# EXT_DIMMER.net
KiCad netlist of a schematic drawn in EAGLE
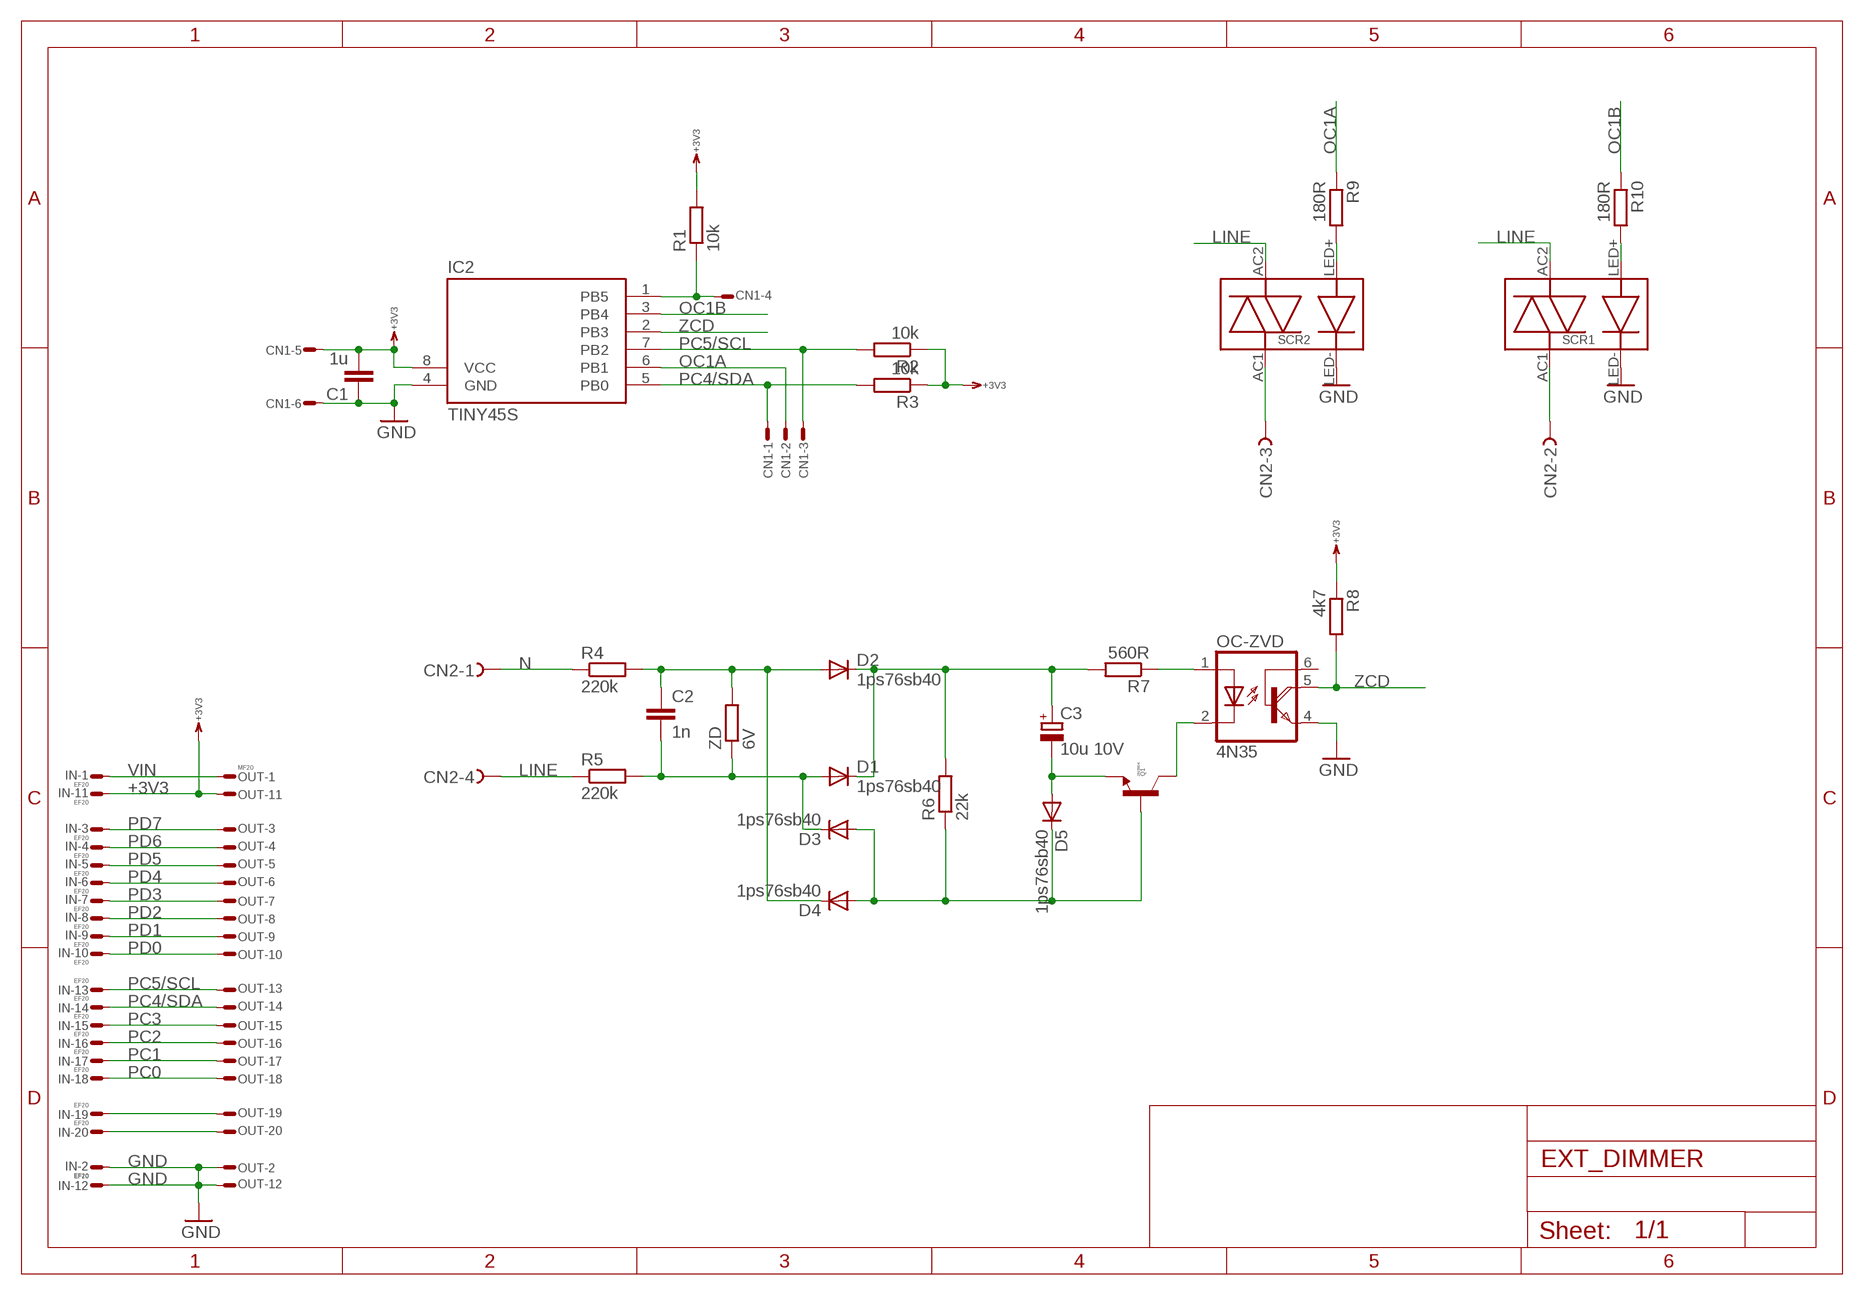
[diagram p0: schematic, sheet 1]

(export (version "E")
  (design (tool "Eeschema 10.0.6"))
  (components
    (comp (ref "C1")
      (value "1u")
      (footprint "eagle-import:0603")
      (libsource (lib "eagle-import") (part "C0603"))
    )
    (comp (ref "C2")
      (value "1n")
      (footprint "eagle-import:1206")
      (libsource (lib "eagle-import") (part "C1206"))
    )
    (comp (ref "C3")
      (value "10u 10V")
      (footprint "eagle-import:SMC_A")
      (libsource (lib "eagle-import") (part "C_POLSMCA"))
    )
    (comp (ref "CN1")
      (value "CON6N")
      (footprint "eagle-import:CON6")
      (libsource (lib "eagle-import") (part "CON6N"))
    )
    (comp (ref "CN2")
      (value "CON4-S")
      (footprint "eagle-import:CTB9308")
      (libsource (lib "eagle-import") (part "CON4-S"))
    )
    (comp (ref "D1")
      (value "1ps76sb40")
      (footprint "eagle-import:SOD323")
      (libsource (lib "eagle-import") (part "DSOD323"))
    )
    (comp (ref "D2")
      (value "1ps76sb40")
      (footprint "eagle-import:SOD323")
      (libsource (lib "eagle-import") (part "DSOD323"))
    )
    (comp (ref "D3")
      (value "1ps76sb40")
      (footprint "eagle-import:SOD323")
      (libsource (lib "eagle-import") (part "DSOD323"))
    )
    (comp (ref "D4")
      (value "1ps76sb40")
      (footprint "eagle-import:SOD323")
      (libsource (lib "eagle-import") (part "DSOD323"))
    )
    (comp (ref "D5")
      (value "1ps76sb40")
      (footprint "eagle-import:SOD323")
      (libsource (lib "eagle-import") (part "DSOD323"))
    )
    (comp (ref "IC2")
      (value "TINY45S")
      (footprint "eagle-import:SOIC8")
      (libsource (lib "eagle-import") (part "TINY45S"))
    )
    (comp (ref "IN")
      (value "EF20")
      (footprint "eagle-import:FE10-2WSS")
      (libsource (lib "eagle-import") (part "FE20ELSS"))
    )
    (comp (ref "OC-ZVD")
      (value "4N35")
      (footprint "eagle-import:DIL06")
      (fields (field (name "MF") "VISHAY/TELEFUNKEN") (field (name "MPN") "4N33"))
      (libsource (lib "eagle-import") (part "OC-NPN"))
    )
    (comp (ref "OUT")
      (value "MF20")
      (footprint "eagle-import:ML20LS")
      (libsource (lib "eagle-import") (part "ML20?ELS"))
    )
    (comp (ref "Q1")
      (value "2N3904")
      (footprint "eagle-import:SOT23")
      (libsource (lib "eagle-import") (part "NPN23"))
    )
    (comp (ref "R1")
      (value "10k")
      (footprint "eagle-import:0603")
      (libsource (lib "eagle-import") (part "R0603"))
    )
    (comp (ref "R2")
      (value "10k")
      (footprint "eagle-import:0603")
      (libsource (lib "eagle-import") (part "R0603"))
    )
    (comp (ref "R3")
      (value "10k")
      (footprint "eagle-import:0603")
      (libsource (lib "eagle-import") (part "R0603"))
    )
    (comp (ref "R4")
      (value "220k")
      (footprint "eagle-import:1206")
      (libsource (lib "eagle-import") (part "R1206"))
    )
    (comp (ref "R5")
      (value "220k")
      (footprint "eagle-import:1206")
      (libsource (lib "eagle-import") (part "R1206"))
    )
    (comp (ref "R6")
      (value "22k")
      (footprint "eagle-import:0603")
      (libsource (lib "eagle-import") (part "R0603"))
    )
    (comp (ref "R7")
      (value "560R")
      (footprint "eagle-import:0603")
      (libsource (lib "eagle-import") (part "R0603"))
    )
    (comp (ref "R8")
      (value "4k7")
      (footprint "eagle-import:0603")
      (libsource (lib "eagle-import") (part "R0603"))
    )
    (comp (ref "R9")
      (value "180R")
      (footprint "eagle-import:0603")
      (libsource (lib "eagle-import") (part "R0603"))
    )
    (comp (ref "R10")
      (value "180R")
      (footprint "eagle-import:0603")
      (libsource (lib "eagle-import") (part "R0603"))
    )
    (comp (ref "SCR1")
      (value "S202")
      (footprint "eagle-import:S202")
      (libsource (lib "eagle-import") (part "S202"))
    )
    (comp (ref "SCR2")
      (value "S202")
      (footprint "eagle-import:S202")
      (libsource (lib "eagle-import") (part "S202"))
    )
    (comp (ref "ZD")
      (value "6V")
      (footprint "eagle-import:1206")
      (libsource (lib "eagle-import") (part "R1206"))
    )
  )
  (nets
    (net (code "1") (name "+3V3") (class "Default")
      (node (ref "C1") (pin "2") (pinfunction "2_2") (pintype "passive"))
      (node (ref "CN1") (pin "5") (pinfunction "S_5") (pintype "passive"))
      (node (ref "IC2") (pin "8") (pinfunction "VCC_8") (pintype "power_in"))
      (node (ref "IN") (pin "P$11") (pinfunction "S_P$11") (pintype "passive"))
      (node (ref "OUT") (pin "P$11") (pinfunction "S_P$11") (pintype "passive"))
      (node (ref "R1") (pin "2") (pinfunction "2_2") (pintype "passive"))
      (node (ref "R2") (pin "1") (pinfunction "1_1") (pintype "passive"))
      (node (ref "R3") (pin "1") (pinfunction "1_1") (pintype "passive"))
      (node (ref "R8") (pin "1") (pinfunction "1_1") (pintype "passive"))
    )
    (net (code "2") (name "/LINE") (class "Default")
      (node (ref "CN2") (pin "-4") (pinfunction "F_-4") (pintype "passive"))
      (node (ref "R5") (pin "1") (pinfunction "1_1") (pintype "passive"))
      (node (ref "SCR1") (pin "AC2") (pinfunction "AC2_AC2") (pintype "bidirectional"))
      (node (ref "SCR2") (pin "AC2") (pinfunction "AC2_AC2") (pintype "bidirectional"))
    )
    (net (code "3") (name "/N") (class "Default")
      (node (ref "CN2") (pin "-1") (pinfunction "F_-1") (pintype "passive"))
      (node (ref "R4") (pin "1") (pinfunction "1_1") (pintype "passive"))
    )
    (net (code "4") (name "/OC1A") (class "Default")
      (node (ref "CN1") (pin "2") (pinfunction "S_2") (pintype "passive"))
      (node (ref "IC2") (pin "6") (pinfunction "PB1_6") (pintype "bidirectional"))
      (node (ref "R9") (pin "1") (pinfunction "1_1") (pintype "passive"))
    )
    (net (code "5") (name "/OC1B") (class "Default")
      (node (ref "IC2") (pin "3") (pinfunction "PB4_3") (pintype "bidirectional"))
      (node (ref "R10") (pin "1") (pinfunction "1_1") (pintype "passive"))
    )
    (net (code "6") (name "/PC0") (class "Default")
      (node (ref "IN") (pin "P$18") (pinfunction "S_P$18") (pintype "passive"))
      (node (ref "OUT") (pin "P$18") (pinfunction "S_P$18") (pintype "passive"))
    )
    (net (code "7") (name "/PC1") (class "Default")
      (node (ref "IN") (pin "P$17") (pinfunction "S_P$17") (pintype "passive"))
      (node (ref "OUT") (pin "P$17") (pinfunction "S_P$17") (pintype "passive"))
    )
    (net (code "8") (name "/PC2") (class "Default")
      (node (ref "IN") (pin "P$16") (pinfunction "S_P$16") (pintype "passive"))
      (node (ref "OUT") (pin "P$16") (pinfunction "S_P$16") (pintype "passive"))
    )
    (net (code "9") (name "/PC3") (class "Default")
      (node (ref "IN") (pin "P$15") (pinfunction "S_P$15") (pintype "passive"))
      (node (ref "OUT") (pin "P$15") (pinfunction "S_P$15") (pintype "passive"))
    )
    (net (code "10") (name "/PC4{slash}SDA") (class "Default")
      (node (ref "CN1") (pin "1") (pinfunction "S_1") (pintype "passive"))
      (node (ref "IC2") (pin "5") (pinfunction "PB0_5") (pintype "bidirectional"))
      (node (ref "IN") (pin "P$14") (pinfunction "S_P$14") (pintype "passive"))
      (node (ref "OUT") (pin "P$14") (pinfunction "S_P$14") (pintype "passive"))
      (node (ref "R3") (pin "2") (pinfunction "2_2") (pintype "passive"))
    )
    (net (code "11") (name "/PC5{slash}SCL") (class "Default")
      (node (ref "CN1") (pin "3") (pinfunction "S_3") (pintype "passive"))
      (node (ref "IC2") (pin "7") (pinfunction "PB2_7") (pintype "bidirectional"))
      (node (ref "IN") (pin "P$13") (pinfunction "S_P$13") (pintype "passive"))
      (node (ref "OUT") (pin "P$13") (pinfunction "S_P$13") (pintype "passive"))
      (node (ref "R2") (pin "2") (pinfunction "2_2") (pintype "passive"))
    )
    (net (code "12") (name "/PD0") (class "Default")
      (node (ref "IN") (pin "P$10") (pinfunction "S_P$10") (pintype "passive"))
      (node (ref "OUT") (pin "P$10") (pinfunction "S_P$10") (pintype "passive"))
    )
    (net (code "13") (name "/PD1") (class "Default")
      (node (ref "IN") (pin "P$9") (pinfunction "S_P$9") (pintype "passive"))
      (node (ref "OUT") (pin "P$9") (pinfunction "S_P$9") (pintype "passive"))
    )
    (net (code "14") (name "/PD2") (class "Default")
      (node (ref "IN") (pin "P$8") (pinfunction "S_P$8") (pintype "passive"))
      (node (ref "OUT") (pin "P$8") (pinfunction "S_P$8") (pintype "passive"))
    )
    (net (code "15") (name "/PD3") (class "Default")
      (node (ref "IN") (pin "P$7") (pinfunction "S_P$7") (pintype "passive"))
      (node (ref "OUT") (pin "P$7") (pinfunction "S_P$7") (pintype "passive"))
    )
    (net (code "16") (name "/PD4") (class "Default")
      (node (ref "IN") (pin "P$6") (pinfunction "S_P$6") (pintype "passive"))
      (node (ref "OUT") (pin "P$6") (pinfunction "S_P$6") (pintype "passive"))
    )
    (net (code "17") (name "/PD5") (class "Default")
      (node (ref "IN") (pin "P$5") (pinfunction "S_P$5") (pintype "passive"))
      (node (ref "OUT") (pin "P$5") (pinfunction "S_P$5") (pintype "passive"))
    )
    (net (code "18") (name "/PD6") (class "Default")
      (node (ref "IN") (pin "P$4") (pinfunction "S_P$4") (pintype "passive"))
      (node (ref "OUT") (pin "P$4") (pinfunction "S_P$4") (pintype "passive"))
    )
    (net (code "19") (name "/PD7") (class "Default")
      (node (ref "IN") (pin "P$3") (pinfunction "S_P$3") (pintype "passive"))
      (node (ref "OUT") (pin "P$3") (pinfunction "S_P$3") (pintype "passive"))
    )
    (net (code "20") (name "/VIN") (class "Default")
      (node (ref "IN") (pin "P$1") (pinfunction "S_P$1") (pintype "passive"))
      (node (ref "OUT") (pin "P$1") (pinfunction "S_P$1") (pintype "passive"))
    )
    (net (code "21") (name "/ZCD") (class "Default")
      (node (ref "IC2") (pin "2") (pinfunction "PB3_2") (pintype "bidirectional"))
      (node (ref "OC-ZVD") (pin "5") (pinfunction "COL_5") (pintype "passive"))
      (node (ref "R8") (pin "2") (pinfunction "2_2") (pintype "passive"))
    )
    (net (code "22") (name "GND") (class "Default")
      (node (ref "C1") (pin "1") (pinfunction "1_1") (pintype "passive"))
      (node (ref "CN1") (pin "6") (pinfunction "S_6") (pintype "passive"))
      (node (ref "IC2") (pin "4") (pinfunction "GND_4") (pintype "power_in"))
      (node (ref "IN") (pin "P$12") (pinfunction "S_P$12") (pintype "passive"))
      (node (ref "IN") (pin "P$2") (pinfunction "S_P$2") (pintype "passive"))
      (node (ref "OC-ZVD") (pin "4") (pinfunction "E_4") (pintype "passive"))
      (node (ref "OUT") (pin "P$12") (pinfunction "S_P$12") (pintype "passive"))
      (node (ref "OUT") (pin "P$2") (pinfunction "S_P$2") (pintype "passive"))
      (node (ref "SCR1") (pin "LED-") (pinfunction "L-_LED-") (pintype "bidirectional"))
      (node (ref "SCR2") (pin "LED-") (pinfunction "L-_LED-") (pintype "bidirectional"))
    )
    (net (code "23") (name "Net-(C2-Pad1)") (class "Default")
      (node (ref "C2") (pin "1") (pinfunction "1_1") (pintype "passive"))
      (node (ref "D2") (pin "A") (pinfunction "A_A") (pintype "passive"))
      (node (ref "D4") (pin "C") (pinfunction "C_C") (pintype "passive"))
      (node (ref "R4") (pin "2") (pinfunction "2_2") (pintype "passive"))
      (node (ref "ZD") (pin "2") (pinfunction "2_2") (pintype "passive"))
    )
    (net (code "24") (name "Net-(C2-Pad2)") (class "Default")
      (node (ref "C2") (pin "2") (pinfunction "2_2") (pintype "passive"))
      (node (ref "D1") (pin "A") (pinfunction "A_A") (pintype "passive"))
      (node (ref "D3") (pin "C") (pinfunction "C_C") (pintype "passive"))
      (node (ref "R5") (pin "2") (pinfunction "2_2") (pintype "passive"))
      (node (ref "ZD") (pin "1") (pinfunction "1_1") (pintype "passive"))
    )
    (net (code "25") (name "Net-(C3-Pad+)") (class "Default")
      (node (ref "C3") (pin "+") (pinfunction "+_+") (pintype "passive"))
      (node (ref "D1") (pin "C") (pinfunction "C_C") (pintype "passive"))
      (node (ref "D2") (pin "C") (pinfunction "C_C") (pintype "passive"))
      (node (ref "R6") (pin "2") (pinfunction "2_2") (pintype "passive"))
      (node (ref "R7") (pin "2") (pinfunction "2_2") (pintype "passive"))
    )
    (net (code "26") (name "Net-(CN1D-S)") (class "Default")
      (node (ref "CN1") (pin "4") (pinfunction "S_4") (pintype "passive"))
      (node (ref "IC2") (pin "1") (pinfunction "PB5_1") (pintype "bidirectional"))
      (node (ref "R1") (pin "1") (pinfunction "1_1") (pintype "passive"))
    )
    (net (code "27") (name "Net-(CN2B-F)") (class "Default")
      (node (ref "CN2") (pin "-2") (pinfunction "F_-2") (pintype "passive"))
      (node (ref "SCR1") (pin "AC1") (pinfunction "AC1_AC1") (pintype "bidirectional"))
    )
    (net (code "28") (name "Net-(CN2C-F)") (class "Default")
      (node (ref "CN2") (pin "-3") (pinfunction "F_-3") (pintype "passive"))
      (node (ref "SCR2") (pin "AC1") (pinfunction "AC1_AC1") (pintype "bidirectional"))
    )
    (net (code "29") (name "Net-(INK-S)") (class "Default")
      (node (ref "IN") (pin "P$19") (pinfunction "S_P$19") (pintype "passive"))
      (node (ref "OUT") (pin "P$19") (pinfunction "S_P$19") (pintype "passive"))
    )
    (net (code "30") (name "Net-(INM-S)") (class "Default")
      (node (ref "IN") (pin "P$20") (pinfunction "S_P$20") (pintype "passive"))
      (node (ref "OUT") (pin "P$20") (pinfunction "S_P$20") (pintype "passive"))
    )
    (net (code "31") (name "Net-(OC-ZVD-A)") (class "Default")
      (node (ref "OC-ZVD") (pin "1") (pinfunction "A_1") (pintype "passive"))
      (node (ref "R7") (pin "1") (pinfunction "1_1") (pintype "passive"))
    )
    (net (code "32") (name "Net-(OC-ZVD-C)") (class "Default")
      (node (ref "OC-ZVD") (pin "2") (pinfunction "C_2") (pintype "passive"))
      (node (ref "Q1") (pin "3") (pinfunction "C_3") (pintype "passive"))
    )
    (net (code "33") (name "Net-(Q1-B)") (class "Default")
      (node (ref "D3") (pin "A") (pinfunction "A_A") (pintype "passive"))
      (node (ref "D4") (pin "A") (pinfunction "A_A") (pintype "passive"))
      (node (ref "D5") (pin "C") (pinfunction "C_C") (pintype "passive"))
      (node (ref "Q1") (pin "1") (pinfunction "B_1") (pintype "passive"))
      (node (ref "R6") (pin "1") (pinfunction "1_1") (pintype "passive"))
    )
    (net (code "34") (name "Net-(Q1-E)") (class "Default")
      (node (ref "C3") (pin "-") (pinfunction "-_-") (pintype "passive"))
      (node (ref "D5") (pin "A") (pinfunction "A_A") (pintype "passive"))
      (node (ref "Q1") (pin "2") (pinfunction "E_2") (pintype "passive"))
    )
    (net (code "35") (name "Net-(SCR1-L+)") (class "Default")
      (node (ref "R10") (pin "2") (pinfunction "2_2") (pintype "passive"))
      (node (ref "SCR1") (pin "LED+") (pinfunction "L+_LED+") (pintype "bidirectional"))
    )
    (net (code "36") (name "Net-(SCR2-L+)") (class "Default")
      (node (ref "R9") (pin "2") (pinfunction "2_2") (pintype "passive"))
      (node (ref "SCR2") (pin "LED+") (pinfunction "L+_LED+") (pintype "bidirectional"))
    )
    (net (code "37") (name "unconnected-(OC-ZVD-B-Pad6)") (class "Default")
      (node (ref "OC-ZVD") (pin "6") (pinfunction "B_6") (pintype "passive"))
    )
  )
)
